# DOG_DisplayBreakout.net
KiCad netlist of a schematic drawn in EAGLE
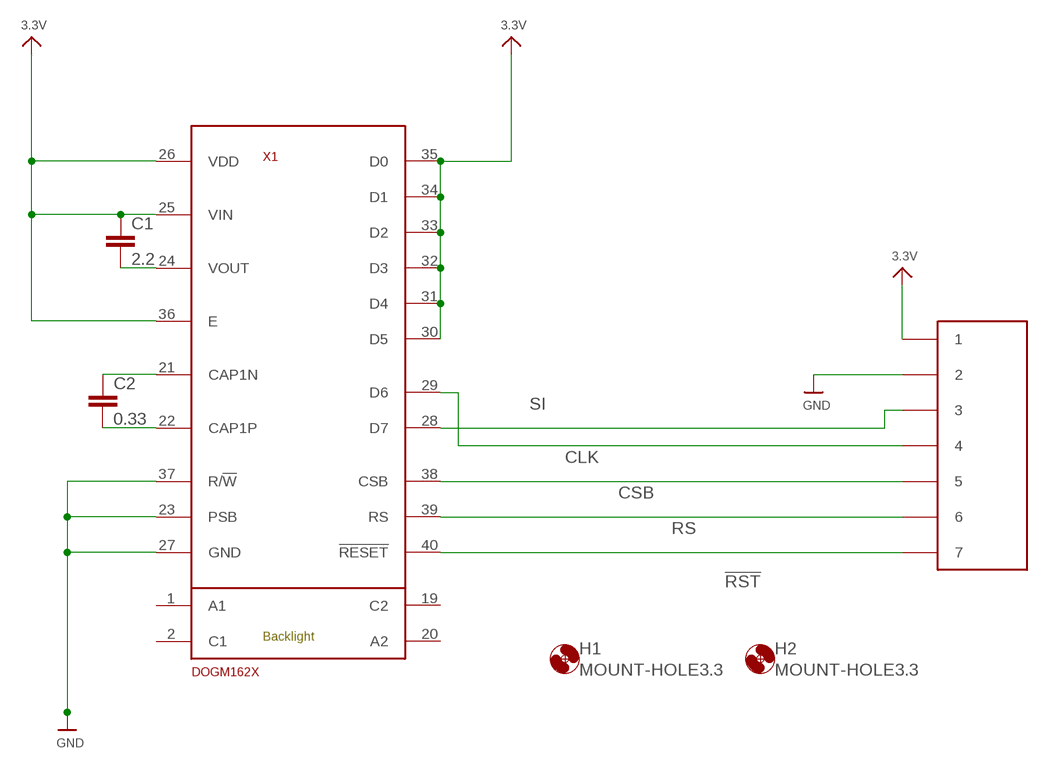
[diagram p0: schematic, sheet 1]

(export (version "E")
  (design (tool "Eeschema 10.0.6"))
  (components
    (comp (ref "C1")
      (value "2.2")
      (footprint "eagle-import:0805_BIGGERPAD-OK")
      (libsource (lib "eagle-import") (part "CAPACITOR0805"))
    )
    (comp (ref "C2")
      (value "0.33")
      (footprint "eagle-import:0805_BIGGERPAD-OK")
      (libsource (lib "eagle-import") (part "CAPACITOR0805"))
    )
    (comp (ref "CN1")
      (value "JST_S7B-PH-K-S")
      (footprint "eagle-import:JST_S7B-PH-K-S")
      (libsource (lib "eagle-import") (part "JST_S7B-PH-K-S"))
    )
    (comp (ref "H1")
      (value "MOUNT-HOLE3.3")
      (footprint "eagle-import:HOLE3,3")
      (libsource (lib "eagle-import") (part "MOUNT-HOLE3.3"))
    )
    (comp (ref "H2")
      (value "MOUNT-HOLE3.3")
      (footprint "eagle-import:HOLE3,3")
      (libsource (lib "eagle-import") (part "MOUNT-HOLE3.3"))
    )
    (comp (ref "X1")
      (value "DOGM162X")
      (footprint "eagle-import:DOGM162X")
      (libsource (lib "eagle-import") (part "DOGM162X"))
    )
  )
  (nets
    (net (code "1") (name "/CLK") (class "Default")
      (node (ref "CN1") (pin "P4") (pinfunction "4_P4") (pintype "bidirectional"))
      (node (ref "X1") (pin "29") (pinfunction "D6_29") (pintype "bidirectional"))
    )
    (net (code "2") (name "/CSB") (class "Default")
      (node (ref "CN1") (pin "P5") (pinfunction "5_P5") (pintype "bidirectional"))
      (node (ref "X1") (pin "38") (pinfunction "CSB_38") (pintype "bidirectional"))
    )
    (net (code "3") (name "/RS") (class "Default")
      (node (ref "CN1") (pin "P6") (pinfunction "6_P6") (pintype "bidirectional"))
      (node (ref "X1") (pin "39") (pinfunction "RS_39") (pintype "bidirectional"))
    )
    (net (code "4") (name "/SI") (class "Default")
      (node (ref "CN1") (pin "P3") (pinfunction "3_P3") (pintype "bidirectional"))
      (node (ref "X1") (pin "28") (pinfunction "D7_28") (pintype "bidirectional"))
    )
    (net (code "5") (name "/~{RST}") (class "Default")
      (node (ref "CN1") (pin "P7") (pinfunction "7_P7") (pintype "bidirectional"))
      (node (ref "X1") (pin "40") (pinfunction "~{RESET}_40") (pintype "bidirectional"))
    )
    (net (code "6") (name "3.3V") (class "Default")
      (node (ref "C1") (pin "1") (pinfunction "1_1") (pintype "passive"))
      (node (ref "CN1") (pin "P1") (pinfunction "1_P1") (pintype "bidirectional"))
      (node (ref "X1") (pin "25") (pinfunction "VIN_25") (pintype "bidirectional"))
      (node (ref "X1") (pin "26") (pinfunction "VDD_26") (pintype "bidirectional"))
      (node (ref "X1") (pin "30") (pinfunction "D5_30") (pintype "bidirectional"))
      (node (ref "X1") (pin "31") (pinfunction "D4_31") (pintype "bidirectional"))
      (node (ref "X1") (pin "32") (pinfunction "D3_32") (pintype "bidirectional"))
      (node (ref "X1") (pin "33") (pinfunction "D2_33") (pintype "bidirectional"))
      (node (ref "X1") (pin "34") (pinfunction "D1_34") (pintype "bidirectional"))
      (node (ref "X1") (pin "35") (pinfunction "D0_35") (pintype "bidirectional"))
      (node (ref "X1") (pin "36") (pinfunction "E_36") (pintype "bidirectional"))
    )
    (net (code "7") (name "GND") (class "Default")
      (node (ref "CN1") (pin "P2") (pinfunction "2_P2") (pintype "bidirectional"))
      (node (ref "X1") (pin "23") (pinfunction "PSB_23") (pintype "bidirectional"))
      (node (ref "X1") (pin "27") (pinfunction "GND_27") (pintype "bidirectional"))
      (node (ref "X1") (pin "37") (pinfunction "R/~{W}_37") (pintype "bidirectional"))
    )
    (net (code "8") (name "Net-(X1-CAP1N)") (class "Default")
      (node (ref "C2") (pin "1") (pinfunction "1_1") (pintype "passive"))
      (node (ref "X1") (pin "21") (pinfunction "CAP1N_21") (pintype "bidirectional"))
    )
    (net (code "9") (name "Net-(X1-CAP1P)") (class "Default")
      (node (ref "C2") (pin "2") (pinfunction "2_2") (pintype "passive"))
      (node (ref "X1") (pin "22") (pinfunction "CAP1P_22") (pintype "bidirectional"))
    )
    (net (code "10") (name "Net-(X1-VOUT)") (class "Default")
      (node (ref "C1") (pin "2") (pinfunction "2_2") (pintype "passive"))
      (node (ref "X1") (pin "24") (pinfunction "VOUT_24") (pintype "bidirectional"))
    )
    (net (code "11") (name "unconnected-(X1-A1-Pad1)") (class "Default")
      (node (ref "X1") (pin "1") (pinfunction "A1_1") (pintype "bidirectional"))
    )
    (net (code "12") (name "unconnected-(X1-A2-Pad20)") (class "Default")
      (node (ref "X1") (pin "20") (pinfunction "A2_20") (pintype "bidirectional"))
    )
    (net (code "13") (name "unconnected-(X1-C1-Pad2)") (class "Default")
      (node (ref "X1") (pin "2") (pinfunction "C1_2") (pintype "bidirectional"))
    )
    (net (code "14") (name "unconnected-(X1-C2-Pad19)") (class "Default")
      (node (ref "X1") (pin "19") (pinfunction "C2_19") (pintype "bidirectional"))
    )
  )
)
